# MX8M-Nano-Misc.net
KiCad netlist of a schematic drawn in Altium Designer
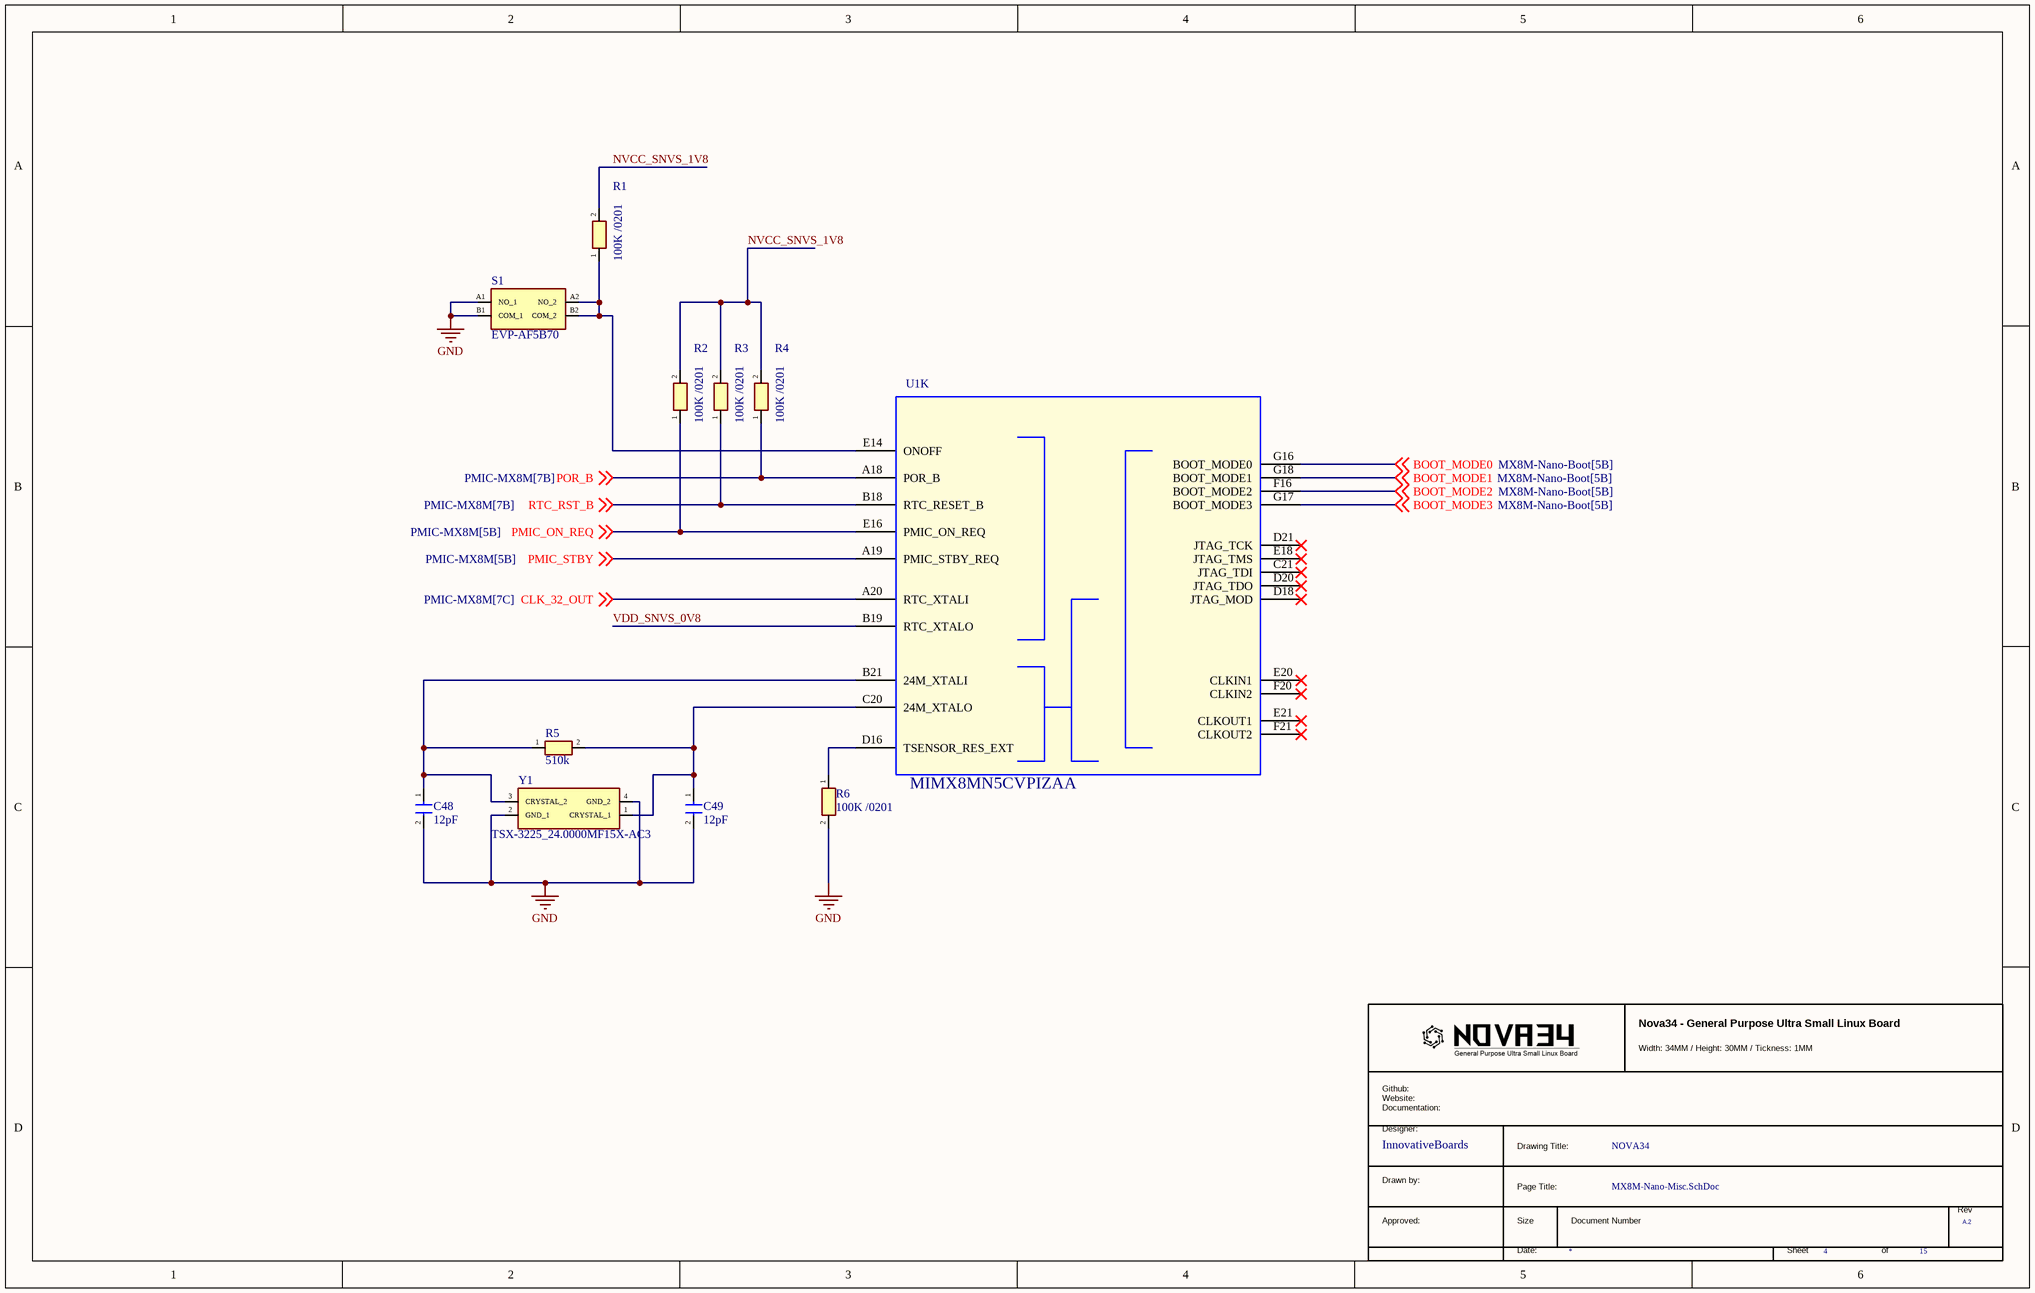
[diagram p0: MX8M-Nano-Misc.SchDoc]

(export (version "E")
  (design (tool "Eeschema 10.0.6"))
  (components
    (comp (ref "*")
      (value "TitleBlock_MCPG")
      (fields (field (name "REVCODE") "A.2"))
      (libsource (lib "Nova_SCHLIB") (part "TitleBlock_MCPG"))
    )
    (comp (ref "C48")
      (value "12pF")
      (footprint "CAPC0603X33N")
      (description "Capacitor")
      (fields
        (field (name "MANUFACTURER_PART_NUMBER") "CGA1A2C0G1E120J030BA")
        (field (name "MOUSER PART NUMBER") "810-CGA1A2C0G1E120J")
      )
      (libsource (lib "Nova_SCHLIB") (part "CGA1A2C0G1E120J030BA"))
    )
    (comp (ref "C49")
      (value "12pF")
      (footprint "CAPC0603X33N")
      (description "Capacitor")
      (fields
        (field (name "MANUFACTURER_PART_NUMBER") "CGA1A2C0G1E120J030BA")
        (field (name "MOUSER PART NUMBER") "810-CGA1A2C0G1E120J")
      )
      (libsource (lib "Nova_SCHLIB") (part "CGA1A2C0G1E120J030BA"))
    )
    (comp (ref "R1")
      (value "100K /0201")
      (footprint "ERJ1GJJ2R4C")
      (description "Resistor")
      (fields
        (field (name "MANUFACTURER_PART_NUMBER") "ERJ-1GJF1003C")
        (field (name "MOUSER PART NUMBER") "667-ERJ-1GJF1003C")
      )
      (libsource (lib "") (part "ERJ-1GJF1003C_1"))
    )
    (comp (ref "R2")
      (value "100K /0201")
      (footprint "ERJ1GJJ2R4C")
      (description "Resistor")
      (fields
        (field (name "MANUFACTURER_PART_NUMBER") "ERJ-1GJF1003C")
        (field (name "MOUSER PART NUMBER") "667-ERJ-1GJF1003C")
      )
      (libsource (lib "") (part "ERJ-1GJF1003C_1"))
    )
    (comp (ref "R3")
      (value "100K /0201")
      (footprint "ERJ1GJJ2R4C")
      (description "Resistor")
      (fields
        (field (name "MANUFACTURER_PART_NUMBER") "ERJ-1GJF1003C")
        (field (name "MOUSER PART NUMBER") "667-ERJ-1GJF1003C")
      )
      (libsource (lib "") (part "ERJ-1GJF1003C_1"))
    )
    (comp (ref "R4")
      (value "100K /0201")
      (footprint "ERJ1GJJ2R4C")
      (description "Resistor")
      (fields
        (field (name "MANUFACTURER_PART_NUMBER") "ERJ-1GJF1003C")
        (field (name "MOUSER PART NUMBER") "667-ERJ-1GJF1003C")
      )
      (libsource (lib "") (part "ERJ-1GJF1003C_1"))
    )
    (comp (ref "R5")
      (value "510k")
      (footprint "ERJ2RKD1004X")
      (description "Resistor")
      (fields
        (field (name "MANUFACTURER_PART_NUMBER") "ERJ-2GEJ514X")
        (field (name "MOUSER PART NUMBER") "667-ERJ-2GEJ514X")
      )
      (libsource (lib "Nova_SCHLIB") (part "ERJ-2GEJ514X"))
    )
    (comp (ref "R6")
      (value "100K /0201")
      (footprint "ERJ1GJJ2R4C")
      (description "Resistor")
      (fields
        (field (name "MANUFACTURER_PART_NUMBER") "ERJ-1GJF1003C")
        (field (name "MOUSER PART NUMBER") "667-ERJ-1GJF1003C")
      )
      (libsource (lib "Nova_SCHLIB") (part "ERJ-1GJF1003C"))
    )
    (comp (ref "S1")
      (value "EVP-AF5B70")
      (footprint "EVPAF5B70")
      (description "Switch")
      (fields (field (name "MOUSER PART NUMBER") "667-EVP-AF5B70"))
      (libsource (lib "Nova_SCHLIB") (part "EVP-AF5B70"))
    )
    (comp (ref "U1")
      (value "MIMX8MN5CVPIZAA")
      (footprint "BGA306C50P21X21_1100X1100X101")
      (description "IC CPU QUAD CORTEX A53+M7 1.4GHZ -- BGA306")
      (libsource (lib "Nova_SCHLIB") (part "MIMX8MN"))
    )
    (comp (ref "Y1")
      (value "TSX-3225_24.0000MF15X-AC3")
      (footprint "TSX3225240000MF15XAC3")
      (description "Crystal or Oscillator")
      (fields
        (field (name "MANUFACTURER_PART_NUMBER") "TSX-3225 24.0000MF15X-AC3")
        (field (name "MOUSER PART NUMBER") "732-TX325-24F15X-AC3")
      )
      (libsource (lib "Nova_SCHLIB") (part "TSX-3225_24.0000MF15X-AC3"))
    )
  )
  (nets
    (net (code "1") (name "/NVCC_SNVS_1V8") (class "Default")
      (node (ref "R1") (pin "2") (pinfunction "2_2") (pintype "passive"))
      (node (ref "R2") (pin "2") (pinfunction "2_2") (pintype "passive"))
      (node (ref "R3") (pin "2") (pinfunction "2_2") (pintype "passive"))
      (node (ref "R4") (pin "2") (pinfunction "2_2") (pintype "passive"))
    )
    (net (code "2") (name "/VDD_SNVS_0V8") (class "Default")
      (node (ref "U1") (pin "B19") (pinfunction "RTC_XTALO_B19") (pintype "passive"))
    )
    (net (code "3") (name "BOOT_MODE0") (class "Default")
      (node (ref "U1") (pin "G16") (pinfunction "BOOT_MODE0_G16") (pintype "passive"))
    )
    (net (code "4") (name "BOOT_MODE1") (class "Default")
      (node (ref "U1") (pin "G18") (pinfunction "BOOT_MODE1_G18") (pintype "passive"))
    )
    (net (code "5") (name "BOOT_MODE2") (class "Default")
      (node (ref "U1") (pin "F16") (pinfunction "BOOT_MODE2_F16") (pintype "passive"))
    )
    (net (code "6") (name "BOOT_MODE3") (class "Default")
      (node (ref "U1") (pin "G17") (pinfunction "BOOT_MODE3_G17") (pintype "passive"))
    )
    (net (code "7") (name "CLK_32_OUT") (class "Default")
      (node (ref "U1") (pin "A20") (pinfunction "RTC_XTALI_A20") (pintype "passive"))
    )
    (net (code "8") (name "GND") (class "Default")
      (node (ref "C48") (pin "2") (pinfunction "2_2") (pintype "passive"))
      (node (ref "C49") (pin "2") (pinfunction "2_2") (pintype "passive"))
      (node (ref "R6") (pin "2") (pinfunction "2_2") (pintype "passive"))
      (node (ref "S1") (pin "A1") (pinfunction "NO_1_A1") (pintype "passive"))
      (node (ref "S1") (pin "B1") (pinfunction "COM_1_B1") (pintype "passive"))
      (node (ref "Y1") (pin "2") (pinfunction "GND_1_2") (pintype "passive"))
      (node (ref "Y1") (pin "4") (pinfunction "GND_2_4") (pintype "passive"))
    )
    (net (code "9") (name "Net-(S1-COM_2)") (class "Default")
      (node (ref "R1") (pin "1") (pinfunction "1_1") (pintype "passive"))
      (node (ref "S1") (pin "A2") (pinfunction "NO_2_A2") (pintype "passive"))
      (node (ref "S1") (pin "B2") (pinfunction "COM_2_B2") (pintype "passive"))
      (node (ref "U1") (pin "E14") (pinfunction "ONOFF_E14") (pintype "passive"))
    )
    (net (code "10") (name "Net-(U1K-24M_XTALI)") (class "Default")
      (node (ref "C48") (pin "1") (pinfunction "1_1") (pintype "passive"))
      (node (ref "R5") (pin "1") (pinfunction "1_1") (pintype "passive"))
      (node (ref "U1") (pin "B21") (pinfunction "24M_XTALI_B21") (pintype "passive"))
      (node (ref "Y1") (pin "3") (pinfunction "CRYSTAL_2_3") (pintype "passive"))
    )
    (net (code "11") (name "Net-(U1K-24M_XTALO)") (class "Default")
      (node (ref "C49") (pin "1") (pinfunction "1_1") (pintype "passive"))
      (node (ref "R5") (pin "2") (pinfunction "2_2") (pintype "passive"))
      (node (ref "U1") (pin "C20") (pinfunction "24M_XTALO_C20") (pintype "passive"))
      (node (ref "Y1") (pin "1") (pinfunction "CRYSTAL_1_1") (pintype "passive"))
    )
    (net (code "12") (name "Net-(U1K-TSENSOR_RES_EXT)") (class "Default")
      (node (ref "R6") (pin "1") (pinfunction "1_1") (pintype "passive"))
      (node (ref "U1") (pin "D16") (pinfunction "TSENSOR_RES_EXT_D16") (pintype "passive"))
    )
    (net (code "13") (name "PMIC_ON_REQ") (class "Default")
      (node (ref "R2") (pin "1") (pinfunction "1_1") (pintype "passive"))
      (node (ref "U1") (pin "E16") (pinfunction "PMIC_ON_REQ_E16") (pintype "passive"))
    )
    (net (code "14") (name "PMIC_STBY") (class "Default")
      (node (ref "U1") (pin "A19") (pinfunction "PMIC_STBY_REQ_A19") (pintype "passive"))
    )
    (net (code "15") (name "POR_B") (class "Default")
      (node (ref "R4") (pin "1") (pinfunction "1_1") (pintype "passive"))
      (node (ref "U1") (pin "A18") (pinfunction "POR_B_A18") (pintype "passive"))
    )
    (net (code "16") (name "RTC_RST_B") (class "Default")
      (node (ref "R3") (pin "1") (pinfunction "1_1") (pintype "passive"))
      (node (ref "U1") (pin "B18") (pinfunction "RTC_RESET_B_B18") (pintype "passive"))
    )
    (net (code "17") (name "unconnected-(U1K-CLKIN1-PadE20)") (class "Default")
      (node (ref "U1") (pin "E20") (pinfunction "CLKIN1_E20") (pintype "passive+no_connect"))
    )
    (net (code "18") (name "unconnected-(U1K-CLKIN2-PadF20)") (class "Default")
      (node (ref "U1") (pin "F20") (pinfunction "CLKIN2_F20") (pintype "passive+no_connect"))
    )
    (net (code "19") (name "unconnected-(U1K-CLKOUT1-PadE21)") (class "Default")
      (node (ref "U1") (pin "E21") (pinfunction "CLKOUT1_E21") (pintype "passive+no_connect"))
    )
    (net (code "20") (name "unconnected-(U1K-CLKOUT2-PadF21)") (class "Default")
      (node (ref "U1") (pin "F21") (pinfunction "CLKOUT2_F21") (pintype "passive+no_connect"))
    )
    (net (code "21") (name "unconnected-(U1K-JTAG_MOD-PadD18)") (class "Default")
      (node (ref "U1") (pin "D18") (pinfunction "JTAG_MOD_D18") (pintype "passive+no_connect"))
    )
    (net (code "22") (name "unconnected-(U1K-JTAG_TCK-PadD21)") (class "Default")
      (node (ref "U1") (pin "D21") (pinfunction "JTAG_TCK_D21") (pintype "passive+no_connect"))
    )
    (net (code "23") (name "unconnected-(U1K-JTAG_TDI-PadC21)") (class "Default")
      (node (ref "U1") (pin "C21") (pinfunction "JTAG_TDI_C21") (pintype "passive+no_connect"))
    )
    (net (code "24") (name "unconnected-(U1K-JTAG_TDO-PadD20)") (class "Default")
      (node (ref "U1") (pin "D20") (pinfunction "JTAG_TDO_D20") (pintype "passive+no_connect"))
    )
    (net (code "25") (name "unconnected-(U1K-JTAG_TMS-PadE18)") (class "Default")
      (node (ref "U1") (pin "E18") (pinfunction "JTAG_TMS_E18") (pintype "passive+no_connect"))
    )
  )
)
